# main_board.net
KiCad netlist of a schematic drawn in EAGLE
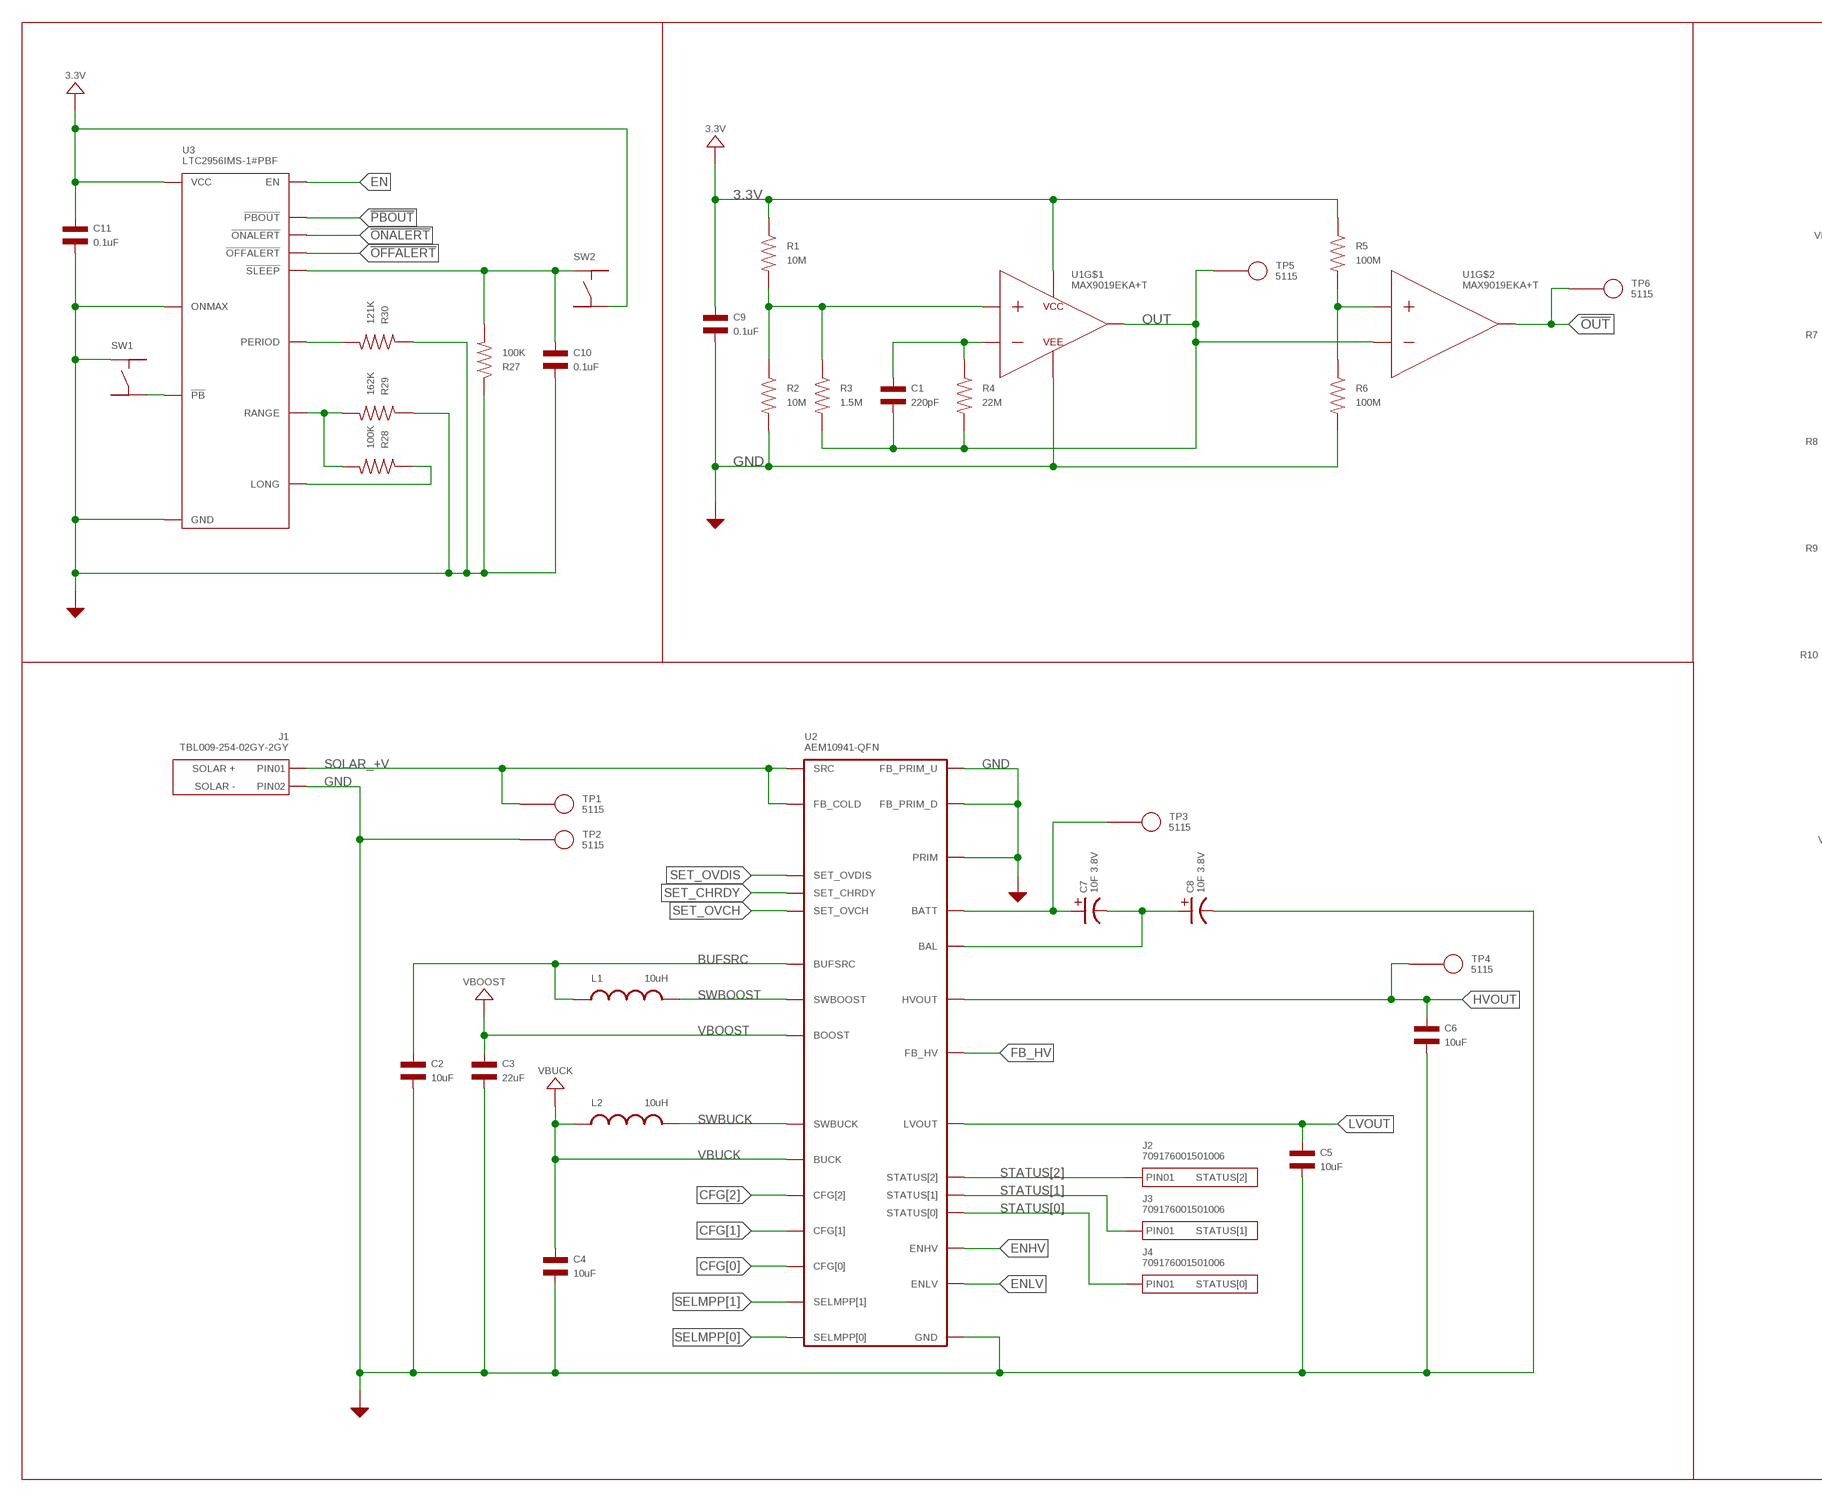
[diagram p0: schematic, sheet 1, part 1 of 2]
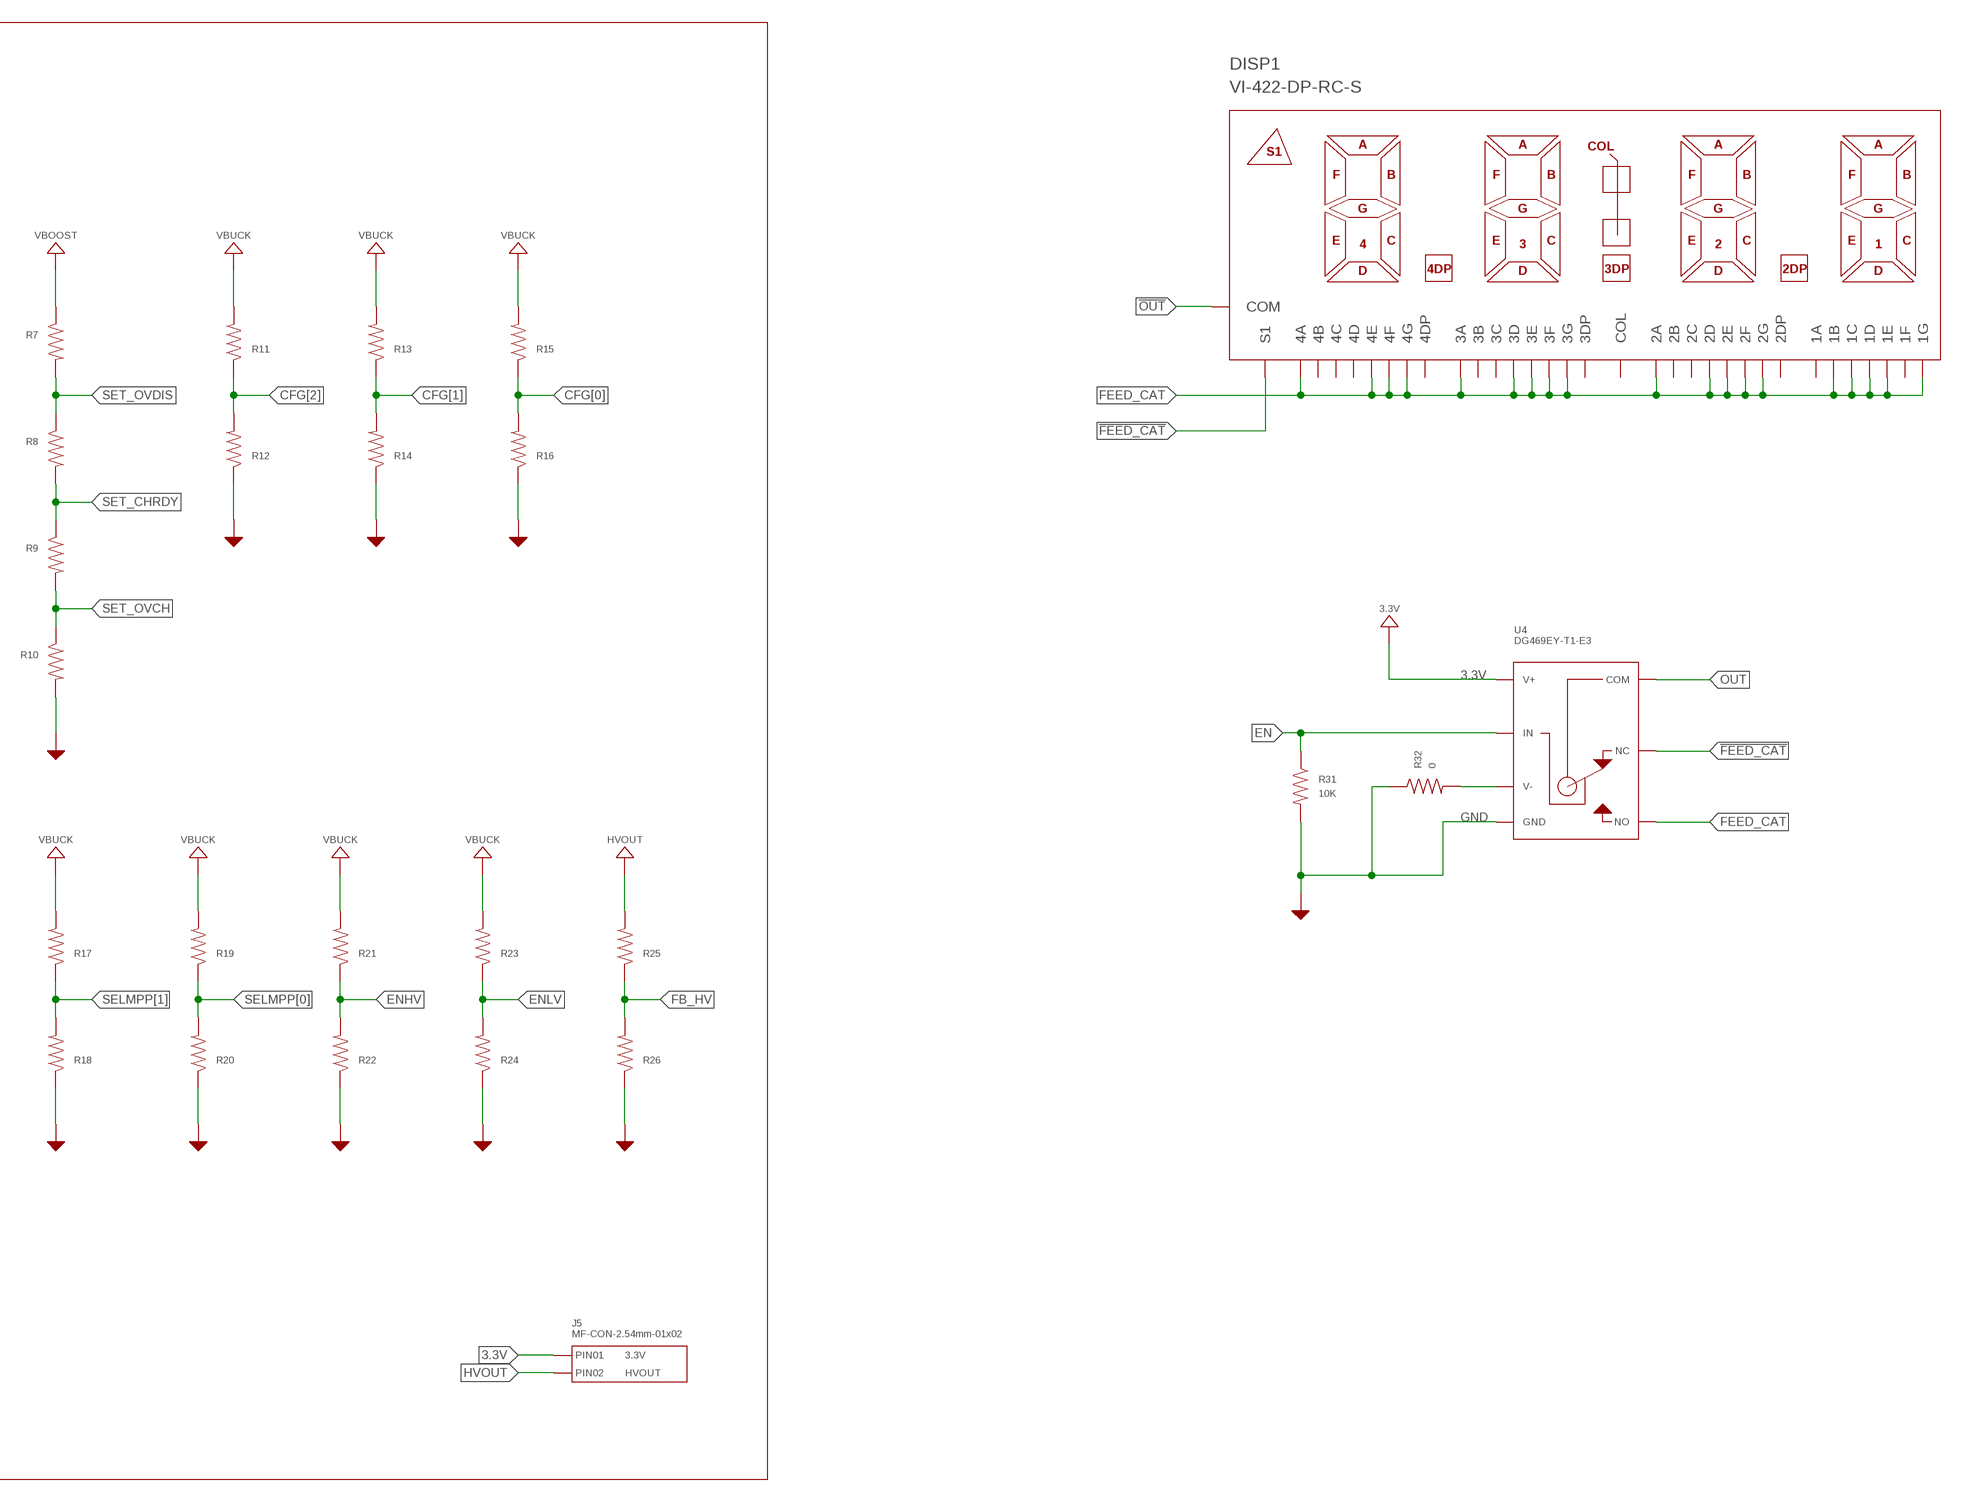
[diagram p1: schematic, sheet 1, part 2 of 2]

(export (version "E")
  (design (tool "Eeschema 10.0.6"))
  (components
    (comp (ref "C1")
      (value "220pF")
      (footprint "eagle-import:C0805")
      (libsource (lib "eagle-import") (part "CAPACITOR_NP_0805"))
    )
    (comp (ref "C2")
      (value "10uF")
      (footprint "eagle-import:C0603")
      (fields (field (name "MPN") "C1608X5R1A106M080AC"))
      (libsource (lib "eagle-import") (part "CAPACITOR_NP_0603"))
    )
    (comp (ref "C3")
      (value "22uF")
      (footprint "eagle-import:C0603")
      (fields (field (name "MPN") "GRM188R61A226ME15D"))
      (libsource (lib "eagle-import") (part "CAPACITOR_NP_0603"))
    )
    (comp (ref "C4")
      (value "10uF")
      (footprint "eagle-import:C0603")
      (fields (field (name "MPN") "C1608X5R1A106M080AC"))
      (libsource (lib "eagle-import") (part "CAPACITOR_NP_0603"))
    )
    (comp (ref "C5")
      (value "10uF")
      (footprint "eagle-import:C0603")
      (fields (field (name "MPN") "C1608X5R1A106M080AC"))
      (libsource (lib "eagle-import") (part "CAPACITOR_NP_0603"))
    )
    (comp (ref "C6")
      (value "10uF")
      (footprint "eagle-import:C0603")
      (fields (field (name "MPN") "C1608X5R1A106M080AC"))
      (libsource (lib "eagle-import") (part "CAPACITOR_NP_0603"))
    )
    (comp (ref "C7")
      (value "10F 3.8V")
      (footprint "eagle-import:12.5MM_CAP_PTH")
      (fields (field (name "MPN") "HSL0814-3R8106-R"))
      (libsource (lib "eagle-import") (part "CAPACITOR_POLARIZED_12.5MM_PTH"))
    )
    (comp (ref "C8")
      (value "10F 3.8V")
      (footprint "eagle-import:12.5MM_CAP_PTH")
      (fields (field (name "MPN") "HSL0814-3R8106-R"))
      (libsource (lib "eagle-import") (part "CAPACITOR_POLARIZED_12.5MM_PTH"))
    )
    (comp (ref "C9")
      (value "0.1uF")
      (footprint "eagle-import:C0603")
      (libsource (lib "eagle-import") (part "CAPACITOR_NP_0603"))
    )
    (comp (ref "C10")
      (value "0.1uF")
      (footprint "eagle-import:C0603")
      (libsource (lib "eagle-import") (part "CAPACITOR_NP_0603"))
    )
    (comp (ref "C11")
      (value "0.1uF")
      (footprint "eagle-import:C0603")
      (libsource (lib "eagle-import") (part "CAPACITOR_NP_0603"))
    )
    (comp (ref "DISP1")
      (value "VI-422-DP-RC-S")
      (footprint "eagle-import:VI-422-DP-RC-S")
      (libsource (lib "eagle-import") (part "VI-422-DP-RC-S"))
    )
    (comp (ref "J1")
      (value "TBL009-254-02GY-2GY")
      (footprint "eagle-import:TBL009-254-02GY-2GY")
      (fields (field (name "LABEL01") "SOLAR +") (field (name "LABEL02") "SOLAR -"))
      (libsource (lib "eagle-import") (part "CON_01X02_TBL009-254-02GY-2GY"))
    )
    (comp (ref "J2")
      (value "709176001501006")
      (footprint "eagle-import:709176001501006")
      (fields (field (name "LABEL01") "STATUS[2]"))
      (libsource (lib "eagle-import") (part "CON_01X01_709176001501006"))
    )
    (comp (ref "J3")
      (value "709176001501006")
      (footprint "eagle-import:709176001501006")
      (fields (field (name "LABEL01") "STATUS[1]"))
      (libsource (lib "eagle-import") (part "CON_01X01_709176001501006"))
    )
    (comp (ref "J4")
      (value "709176001501006")
      (footprint "eagle-import:709176001501006")
      (fields (field (name "LABEL01") "STATUS[0]"))
      (libsource (lib "eagle-import") (part "CON_01X01_709176001501006"))
    )
    (comp (ref "J5")
      (value "MF-CON-2.54mm-01x02")
      (footprint "eagle-import:PTH_2.54MM_01X02")
      (fields
        (field (name "HOUSEPART") "YES")
        (field (name "LABEL01") "3.3V")
        (field (name "LABEL02") "HVOUT")
      )
      (libsource (lib "eagle-import") (part "CON_01X02_PTH_2.54MM"))
    )
    (comp (ref "L1")
      (value "10uH")
      (footprint "eagle-import:LPS4012")
      (fields (field (name "MPN") "LPS4012-103MRC "))
      (libsource (lib "eagle-import") (part "INDUCTORLPS4012"))
    )
    (comp (ref "L2")
      (value "10uH")
      (footprint "eagle-import:0603")
      (fields (field (name "MPN") "MLZ1608M100WT"))
      (libsource (lib "eagle-import") (part "INDUCTOR_0603"))
    )
    (comp (ref "R1")
      (value "10M")
      (footprint "eagle-import:R0805")
      (libsource (lib "eagle-import") (part "RESISTOR_0805"))
    )
    (comp (ref "R2")
      (value "10M")
      (footprint "eagle-import:R0805")
      (libsource (lib "eagle-import") (part "RESISTOR_0805"))
    )
    (comp (ref "R3")
      (value "1.5M")
      (footprint "eagle-import:R0805")
      (libsource (lib "eagle-import") (part "RESISTOR_0805"))
    )
    (comp (ref "R4")
      (value "22M")
      (footprint "eagle-import:R0805")
      (libsource (lib "eagle-import") (part "RESISTOR_0805"))
    )
    (comp (ref "R5")
      (value "100M")
      (footprint "eagle-import:R0805")
      (libsource (lib "eagle-import") (part "RESISTOR_0805"))
    )
    (comp (ref "R6")
      (value "100M")
      (footprint "eagle-import:R0805")
      (libsource (lib "eagle-import") (part "RESISTOR_0805"))
    )
    (comp (ref "R7")
      (value "RESISTOR_0805")
      (footprint "eagle-import:R0805")
      (fields (field (name "POPULATE") "0"))
      (libsource (lib "eagle-import") (part "RESISTOR_0805"))
    )
    (comp (ref "R8")
      (value "RESISTOR_0805")
      (footprint "eagle-import:R0805")
      (fields (field (name "POPULATE") "0"))
      (libsource (lib "eagle-import") (part "RESISTOR_0805"))
    )
    (comp (ref "R9")
      (value "RESISTOR_0805")
      (footprint "eagle-import:R0805")
      (fields (field (name "POPULATE") "0"))
      (libsource (lib "eagle-import") (part "RESISTOR_0805"))
    )
    (comp (ref "R10")
      (value "RESISTOR_0805")
      (footprint "eagle-import:R0805")
      (fields (field (name "POPULATE") "0"))
      (libsource (lib "eagle-import") (part "RESISTOR_0805"))
    )
    (comp (ref "R11")
      (value "RESISTOR_0805")
      (footprint "eagle-import:R0805")
      (fields (field (name "POPULATE") "0"))
      (libsource (lib "eagle-import") (part "RESISTOR_0805"))
    )
    (comp (ref "R12")
      (value "RESISTOR_0805")
      (footprint "eagle-import:R0805")
      (fields (field (name "POPULATE") "0"))
      (libsource (lib "eagle-import") (part "RESISTOR_0805"))
    )
    (comp (ref "R13")
      (value "RESISTOR_0805")
      (footprint "eagle-import:R0805")
      (fields (field (name "POPULATE") "0"))
      (libsource (lib "eagle-import") (part "RESISTOR_0805"))
    )
    (comp (ref "R14")
      (value "RESISTOR_0805")
      (footprint "eagle-import:R0805")
      (fields (field (name "POPULATE") "0"))
      (libsource (lib "eagle-import") (part "RESISTOR_0805"))
    )
    (comp (ref "R15")
      (value "RESISTOR_0805")
      (footprint "eagle-import:R0805")
      (fields (field (name "POPULATE") "0"))
      (libsource (lib "eagle-import") (part "RESISTOR_0805"))
    )
    (comp (ref "R16")
      (value "RESISTOR_0805")
      (footprint "eagle-import:R0805")
      (fields (field (name "POPULATE") "0"))
      (libsource (lib "eagle-import") (part "RESISTOR_0805"))
    )
    (comp (ref "R17")
      (value "RESISTOR_0805")
      (footprint "eagle-import:R0805")
      (fields (field (name "POPULATE") "0"))
      (libsource (lib "eagle-import") (part "RESISTOR_0805"))
    )
    (comp (ref "R18")
      (value "RESISTOR_0805")
      (footprint "eagle-import:R0805")
      (fields (field (name "POPULATE") "0"))
      (libsource (lib "eagle-import") (part "RESISTOR_0805"))
    )
    (comp (ref "R19")
      (value "RESISTOR_0805")
      (footprint "eagle-import:R0805")
      (fields (field (name "POPULATE") "0"))
      (libsource (lib "eagle-import") (part "RESISTOR_0805"))
    )
    (comp (ref "R20")
      (value "RESISTOR_0805")
      (footprint "eagle-import:R0805")
      (fields (field (name "POPULATE") "0"))
      (libsource (lib "eagle-import") (part "RESISTOR_0805"))
    )
    (comp (ref "R21")
      (value "RESISTOR_0805")
      (footprint "eagle-import:R0805")
      (fields (field (name "POPULATE") "0"))
      (libsource (lib "eagle-import") (part "RESISTOR_0805"))
    )
    (comp (ref "R22")
      (value "RESISTOR_0805")
      (footprint "eagle-import:R0805")
      (fields (field (name "POPULATE") "0"))
      (libsource (lib "eagle-import") (part "RESISTOR_0805"))
    )
    (comp (ref "R23")
      (value "RESISTOR_0805")
      (footprint "eagle-import:R0805")
      (fields (field (name "POPULATE") "0"))
      (libsource (lib "eagle-import") (part "RESISTOR_0805"))
    )
    (comp (ref "R24")
      (value "RESISTOR_0805")
      (footprint "eagle-import:R0805")
      (fields (field (name "POPULATE") "0"))
      (libsource (lib "eagle-import") (part "RESISTOR_0805"))
    )
    (comp (ref "R25")
      (value "RESISTOR_0805")
      (footprint "eagle-import:R0805")
      (fields (field (name "POPULATE") "0"))
      (libsource (lib "eagle-import") (part "RESISTOR_0805"))
    )
    (comp (ref "R26")
      (value "RESISTOR_0805")
      (footprint "eagle-import:R0805")
      (fields (field (name "POPULATE") "0"))
      (libsource (lib "eagle-import") (part "RESISTOR_0805"))
    )
    (comp (ref "R27")
      (value "100K")
      (footprint "eagle-import:R0805")
      (fields (field (name "HOUSEPART") "ERA-3ARB104V") (field (name "POPULATE") "0"))
      (libsource (lib "eagle-import") (part "RESISTOR_0805"))
    )
    (comp (ref "R28")
      (value "100K")
      (footprint "eagle-import:R0805")
      (fields (field (name "MPN") "ERA-3ARB104V") (field (name "POPULATE") "0"))
      (libsource (lib "eagle-import") (part "RESISTOR_0805"))
    )
    (comp (ref "R29")
      (value "162K")
      (footprint "eagle-import:R0805")
      (fields (field (name "MPN") "ERA-3AEB1623V") (field (name "POPULATE") "0"))
      (libsource (lib "eagle-import") (part "RESISTOR_0805"))
    )
    (comp (ref "R30")
      (value "121K")
      (footprint "eagle-import:R0805")
      (fields (field (name "MPN") "ERA-3AEB1213V") (field (name "POPULATE") "0"))
      (libsource (lib "eagle-import") (part "RESISTOR_0805"))
    )
    (comp (ref "R31")
      (value "10K")
      (footprint "eagle-import:R0805")
      (fields (field (name "POPULATE") "0"))
      (libsource (lib "eagle-import") (part "RESISTOR_0805"))
    )
    (comp (ref "R32")
      (value "0")
      (footprint "eagle-import:R0805")
      (fields (field (name "POPULATE") "0"))
      (libsource (lib "eagle-import") (part "RESISTOR_0805"))
    )
    (comp (ref "SW1")
      (value "TACT_4.2MM")
      (footprint "eagle-import:TACT4.2MM")
      (fields
        (field (name "HOUSEPART") "YES")
        (field (name "MPN") "MF-SW-TACT-4.2MM")
        (field (name "MPN_1") "PTS810 SJM 250 SMTR LFS")
      )
      (libsource (lib "eagle-import") (part "TACT_4.2MM"))
    )
    (comp (ref "SW2")
      (value "TACT_4.2MM")
      (footprint "eagle-import:TACT4.2MM")
      (fields
        (field (name "HOUSEPART") "YES")
        (field (name "MPN") "MF-SW-TACT-4.2MM")
        (field (name "MPN_1") "PTS810 SJM 250 SMTR LFS")
      )
      (libsource (lib "eagle-import") (part "TACT_4.2MM"))
    )
    (comp (ref "TP1")
      (value "5115")
      (footprint "eagle-import:KEYSTONE_5115-5119")
      (fields (field (name "LABEL01") "SOLAR V+"))
      (libsource (lib "eagle-import") (part "TEST_POINT_SINGLE_KEYSTONE_5115-5119"))
    )
    (comp (ref "TP2")
      (value "5115")
      (footprint "eagle-import:KEYSTONE_5115-5119")
      (fields (field (name "LABEL01") "GND"))
      (libsource (lib "eagle-import") (part "TEST_POINT_SINGLE_KEYSTONE_5115-5119"))
    )
    (comp (ref "TP3")
      (value "5115")
      (footprint "eagle-import:KEYSTONE_5115-5119")
      (fields (field (name "LABEL01") "CAP V+"))
      (libsource (lib "eagle-import") (part "TEST_POINT_SINGLE_KEYSTONE_5115-5119"))
    )
    (comp (ref "TP4")
      (value "5115")
      (footprint "eagle-import:KEYSTONE_5115-5119")
      (fields (field (name "LABEL01") "HVOUT"))
      (libsource (lib "eagle-import") (part "TEST_POINT_SINGLE_KEYSTONE_5115-5119"))
    )
    (comp (ref "TP5")
      (value "5115")
      (footprint "eagle-import:KEYSTONE_5115-5119")
      (fields (field (name "LABEL01") "OUT"))
      (libsource (lib "eagle-import") (part "TEST_POINT_SINGLE_KEYSTONE_5115-5119"))
    )
    (comp (ref "TP6")
      (value "5115")
      (footprint "eagle-import:KEYSTONE_5115-5119")
      (fields (field (name "LABEL01") "!OUT"))
      (libsource (lib "eagle-import") (part "TEST_POINT_SINGLE_KEYSTONE_5115-5119"))
    )
    (comp (ref "U1")
      (value "MAX9019EKA+T")
      (footprint "eagle-import:MAX9019EKA+T")
      (libsource (lib "eagle-import") (part "MAX9019"))
    )
    (comp (ref "U2")
      (value "AEM10941-QFN")
      (footprint "eagle-import:AEM10941_QFN-28")
      (fields (field (name "MPN") "AEM10941"))
      (libsource (lib "eagle-import") (part "AEM10941"))
    )
    (comp (ref "U3")
      (value "LTC2956IMS-1#PBF")
      (footprint "eagle-import:LTC2956_MSOP-12")
      (fields (field (name "MPN") "LTC2956IMS-1#PBF "))
      (libsource (lib "eagle-import") (part "LTC2956IMS-1#PBF"))
    )
    (comp (ref "U4")
      (value "DG469EY-T1-E3")
      (footprint "eagle-import:DG469_SOIC-8")
      (libsource (lib "eagle-import") (part "DG469EY-T1-E3"))
    )
  )
  (nets
    (net (code "1") (name "/BUFSRC") (class "Default")
      (node (ref "C2") (pin "P$1") (pinfunction "P$1_P$1") (pintype "passive"))
      (node (ref "L1") (pin "P$2") (pinfunction "P$2_P$2") (pintype "bidirectional"))
      (node (ref "U2") (pin "P$27") (pinfunction "BUFSRC_P$27") (pintype "bidirectional"))
    )
    (net (code "2") (name "/SOLAR_+V") (class "Default")
      (node (ref "J1") (pin "1A") (pinfunction "PIN1_1A") (pintype "bidirectional"))
      (node (ref "J1") (pin "1B") (pinfunction "PIN1_1B") (pintype "bidirectional"))
      (node (ref "TP1") (pin "P$1") (pinfunction "P$1_P$1") (pintype "bidirectional"))
      (node (ref "U2") (pin "P$25") (pinfunction "SRC_P$25") (pintype "bidirectional"))
      (node (ref "U2") (pin "P$26") (pinfunction "FB_COLD_P$26") (pintype "bidirectional"))
    )
    (net (code "3") (name "/STATUS[0]") (class "Default")
      (node (ref "J4") (pin "P$1") (pinfunction "PIN1_P$1") (pintype "bidirectional"))
      (node (ref "U2") (pin "P$21") (pinfunction "STATUS[0]_P$21") (pintype "bidirectional"))
    )
    (net (code "4") (name "/STATUS[1]") (class "Default")
      (node (ref "J3") (pin "P$1") (pinfunction "PIN1_P$1") (pintype "bidirectional"))
      (node (ref "U2") (pin "P$20") (pinfunction "STATUS[1]_P$20") (pintype "bidirectional"))
    )
    (net (code "5") (name "/STATUS[2]") (class "Default")
      (node (ref "J2") (pin "P$1") (pinfunction "PIN1_P$1") (pintype "bidirectional"))
      (node (ref "U2") (pin "P$19") (pinfunction "STATUS[2]_P$19") (pintype "bidirectional"))
    )
    (net (code "6") (name "/SWBOOST") (class "Default")
      (node (ref "L1") (pin "P$1") (pinfunction "P$1_P$1") (pintype "bidirectional"))
      (node (ref "U2") (pin "P$28") (pinfunction "SWBOOST_P$28") (pintype "bidirectional"))
    )
    (net (code "7") (name "/SWBUCK") (class "Default")
      (node (ref "L2") (pin "1") (pinfunction "P$1_1") (pintype "bidirectional"))
      (node (ref "U2") (pin "P$2") (pinfunction "SWBUCK_P$2") (pintype "bidirectional"))
    )
    (net (code "8") (name "/~{FEED_CAT}") (class "Default")
      (node (ref "DISP1") (pin "P$38") (pinfunction "S1_P$38") (pintype "bidirectional"))
      (node (ref "U4") (pin "P$2") (pinfunction "NC_P$2") (pintype "bidirectional"))
    )
    (net (code "9") (name "/~{OFFALERT}") (class "Default")
      (node (ref "U3") (pin "P$10") (pinfunction "~{OFFALERT}_P$10") (pintype "bidirectional"))
    )
    (net (code "10") (name "/~{ONALERT}") (class "Default")
      (node (ref "U3") (pin "P$12") (pinfunction "~{ONALERT}_P$12") (pintype "bidirectional"))
    )
    (net (code "11") (name "/~{OUT}") (class "Default")
      (node (ref "DISP1") (pin "P$1") (pinfunction "COM_P$1") (pintype "bidirectional"))
      (node (ref "DISP1") (pin "P$40") (pinfunction "COM_P$40") (pintype "bidirectional"))
      (node (ref "TP6") (pin "P$1") (pinfunction "P$1_P$1") (pintype "bidirectional"))
      (node (ref "U1") (pin "P$7") (pinfunction "OUTPUT_2_P$7") (pintype "bidirectional"))
    )
    (net (code "12") (name "/~{PBOUT}") (class "Default")
      (node (ref "U3") (pin "P$9") (pinfunction "~{PBOUT}_P$9") (pintype "bidirectional"))
    )
    (net (code "13") (name "3.3V") (class "Default")
      (node (ref "C11") (pin "P$1") (pinfunction "P$1_P$1") (pintype "passive"))
      (node (ref "C9") (pin "P$1") (pinfunction "P$1_P$1") (pintype "passive"))
      (node (ref "J5") (pin "P$1") (pinfunction "PIN1_P$1") (pintype "bidirectional"))
      (node (ref "R1") (pin "P$1") (pinfunction "P$1_P$1") (pintype "passive"))
      (node (ref "R5") (pin "P$1") (pinfunction "P$1_P$1") (pintype "passive"))
      (node (ref "SW2") (pin "P$4") (pinfunction "P$4_P$4") (pintype "bidirectional"))
      (node (ref "U1") (pin "P$8") (pinfunction "VCC_P$8") (pintype "bidirectional"))
      (node (ref "U3") (pin "P$5") (pinfunction "VCC_P$5") (pintype "bidirectional"))
      (node (ref "U4") (pin "P$4") (pinfunction "V+_P$4") (pintype "bidirectional"))
    )
    (net (code "14") (name "CFG[0]") (class "Default")
      (node (ref "R15") (pin "P$1") (pinfunction "P$1_P$1") (pintype "passive"))
      (node (ref "R16") (pin "P$2") (pinfunction "P$2_P$2") (pintype "passive"))
      (node (ref "U2") (pin "P$6") (pinfunction "CFG[0]_P$6") (pintype "bidirectional"))
    )
    (net (code "15") (name "CFG[1]") (class "Default")
      (node (ref "R13") (pin "P$1") (pinfunction "P$1_P$1") (pintype "passive"))
      (node (ref "R14") (pin "P$2") (pinfunction "P$2_P$2") (pintype "passive"))
      (node (ref "U2") (pin "P$5") (pinfunction "CFG[1]_P$5") (pintype "bidirectional"))
    )
    (net (code "16") (name "CFG[2]") (class "Default")
      (node (ref "R11") (pin "P$1") (pinfunction "P$1_P$1") (pintype "passive"))
      (node (ref "R12") (pin "P$2") (pinfunction "P$2_P$2") (pintype "passive"))
      (node (ref "U2") (pin "P$4") (pinfunction "CFG[2]_P$4") (pintype "bidirectional"))
    )
    (net (code "17") (name "EN") (class "Default")
      (node (ref "R31") (pin "P$1") (pinfunction "P$1_P$1") (pintype "passive"))
      (node (ref "U3") (pin "P$8") (pinfunction "EN_P$8") (pintype "bidirectional"))
      (node (ref "U4") (pin "P$6") (pinfunction "IN_P$6") (pintype "bidirectional"))
    )
    (net (code "18") (name "ENHV") (class "Default")
      (node (ref "R21") (pin "P$1") (pinfunction "P$1_P$1") (pintype "passive"))
      (node (ref "R22") (pin "P$2") (pinfunction "P$2_P$2") (pintype "passive"))
      (node (ref "U2") (pin "P$12") (pinfunction "ENHV_P$12") (pintype "bidirectional"))
    )
    (net (code "19") (name "ENLV") (class "Default")
      (node (ref "R23") (pin "P$1") (pinfunction "P$1_P$1") (pintype "passive"))
      (node (ref "R24") (pin "P$2") (pinfunction "P$2_P$2") (pintype "passive"))
      (node (ref "U2") (pin "P$18") (pinfunction "ENLV_P$18") (pintype "bidirectional"))
    )
    (net (code "20") (name "FB_HV") (class "Default")
      (node (ref "R25") (pin "P$1") (pinfunction "P$1_P$1") (pintype "passive"))
      (node (ref "R26") (pin "P$2") (pinfunction "P$2_P$2") (pintype "passive"))
      (node (ref "U2") (pin "P$13") (pinfunction "FB_HV_P$13") (pintype "bidirectional"))
    )
    (net (code "21") (name "FEED_CAT") (class "Default")
      (node (ref "DISP1") (pin "P$10") (pinfunction "3D_P$10") (pintype "bidirectional"))
      (node (ref "DISP1") (pin "P$13") (pinfunction "2E_P$13") (pintype "bidirectional"))
      (node (ref "DISP1") (pin "P$14") (pinfunction "2D_P$14") (pintype "bidirectional"))
      (node (ref "DISP1") (pin "P$17") (pinfunction "1E_P$17") (pintype "bidirectional"))
      (node (ref "DISP1") (pin "P$18") (pinfunction "1D_P$18") (pintype "bidirectional"))
      (node (ref "DISP1") (pin "P$19") (pinfunction "1C_P$19") (pintype "bidirectional"))
      (node (ref "DISP1") (pin "P$20") (pinfunction "1B_P$20") (pintype "bidirectional"))
      (node (ref "DISP1") (pin "P$23") (pinfunction "1G_P$23") (pintype "bidirectional"))
      (node (ref "DISP1") (pin "P$25") (pinfunction "2A_P$25") (pintype "bidirectional"))
      (node (ref "DISP1") (pin "P$26") (pinfunction "2F_P$26") (pintype "bidirectional"))
      (node (ref "DISP1") (pin "P$27") (pinfunction "2G_P$27") (pintype "bidirectional"))
      (node (ref "DISP1") (pin "P$30") (pinfunction "3A_P$30") (pintype "bidirectional"))
      (node (ref "DISP1") (pin "P$31") (pinfunction "3F_P$31") (pintype "bidirectional"))
      (node (ref "DISP1") (pin "P$32") (pinfunction "3G_P$32") (pintype "bidirectional"))
      (node (ref "DISP1") (pin "P$35") (pinfunction "4A_P$35") (pintype "bidirectional"))
      (node (ref "DISP1") (pin "P$36") (pinfunction "4F_P$36") (pintype "bidirectional"))
      (node (ref "DISP1") (pin "P$37") (pinfunction "4G_P$37") (pintype "bidirectional"))
      (node (ref "DISP1") (pin "P$5") (pinfunction "4E_P$5") (pintype "bidirectional"))
      (node (ref "DISP1") (pin "P$9") (pinfunction "3E_P$9") (pintype "bidirectional"))
      (node (ref "U4") (pin "P$8") (pinfunction "NO_P$8") (pintype "bidirectional"))
    )
    (net (code "22") (name "GND_RAIL") (class "Default")
      (node (ref "C10") (pin "P$2") (pinfunction "P$2_P$2") (pintype "passive"))
      (node (ref "C11") (pin "P$2") (pinfunction "P$2_P$2") (pintype "passive"))
      (node (ref "C2") (pin "P$2") (pinfunction "P$2_P$2") (pintype "passive"))
      (node (ref "C3") (pin "P$2") (pinfunction "P$2_P$2") (pintype "passive"))
      (node (ref "C4") (pin "P$2") (pinfunction "P$2_P$2") (pintype "passive"))
      (node (ref "C5") (pin "P$2") (pinfunction "P$2_P$2") (pintype "passive"))
      (node (ref "C6") (pin "P$2") (pinfunction "P$2_P$2") (pintype "passive"))
      (node (ref "C8") (pin "NEG") (pinfunction "NEG_NEG") (pintype "bidirectional"))
      (node (ref "C9") (pin "P$2") (pinfunction "P$2_P$2") (pintype "passive"))
      (node (ref "J1") (pin "2A") (pinfunction "PIN2_2A") (pintype "bidirectional"))
      (node (ref "J1") (pin "2B") (pinfunction "PIN2_2B") (pintype "bidirectional"))
      (node (ref "R10") (pin "P$2") (pinfunction "P$2_P$2") (pintype "passive"))
      (node (ref "R12") (pin "P$1") (pinfunction "P$1_P$1") (pintype "passive"))
      (node (ref "R14") (pin "P$1") (pinfunction "P$1_P$1") (pintype "passive"))
      (node (ref "R16") (pin "P$1") (pinfunction "P$1_P$1") (pintype "passive"))
      (node (ref "R18") (pin "P$1") (pinfunction "P$1_P$1") (pintype "passive"))
      (node (ref "R2") (pin "P$2") (pinfunction "P$2_P$2") (pintype "passive"))
      (node (ref "R20") (pin "P$1") (pinfunction "P$1_P$1") (pintype "passive"))
      (node (ref "R22") (pin "P$1") (pinfunction "P$1_P$1") (pintype "passive"))
      (node (ref "R24") (pin "P$1") (pinfunction "P$1_P$1") (pintype "passive"))
      (node (ref "R26") (pin "P$1") (pinfunction "P$1_P$1") (pintype "passive"))
      (node (ref "R27") (pin "P$1") (pinfunction "P$1_P$1") (pintype "passive"))
      (node (ref "R29") (pin "P$1") (pinfunction "P$1_P$1") (pintype "passive"))
      (node (ref "R30") (pin "P$1") (pinfunction "P$1_P$1") (pintype "passive"))
      (node (ref "R31") (pin "P$2") (pinfunction "P$2_P$2") (pintype "passive"))
      (node (ref "R32") (pin "P$1") (pinfunction "P$1_P$1") (pintype "passive"))
      (node (ref "R6") (pin "P$2") (pinfunction "P$2_P$2") (pintype "passive"))
      (node (ref "SW1") (pin "P$1") (pinfunction "P$1_P$1") (pintype "bidirectional"))
      (node (ref "TP2") (pin "P$1") (pinfunction "P$1_P$1") (pintype "bidirectional"))
      (node (ref "U1") (pin "P$4") (pinfunction "VEE_P$4") (pintype "bidirectional"))
      (node (ref "U2") (pin "P$10") (pinfunction "FB_PRIM_U_P$10") (pintype "bidirectional"))
      (node (ref "U2") (pin "P$17") (pinfunction "PRIM_P$17") (pintype "bidirectional"))
      (node (ref "U2") (pin "P$29") (pinfunction "GND_P$29") (pintype "bidirectional"))
      (node (ref "U2") (pin "P$9") (pinfunction "FB_PRIM_D_P$9") (pintype "bidirectional"))
      (node (ref "U3") (pin "P$1") (pinfunction "ONMAX_P$1") (pintype "bidirectional"))
      (node (ref "U3") (pin "P$6") (pinfunction "GND_P$6") (pintype "bidirectional"))
      (node (ref "U4") (pin "P$3") (pinfunction "GND_P$3") (pintype "bidirectional"))
    )
    (net (code "23") (name "HVOUT") (class "Default")
      (node (ref "C6") (pin "P$1") (pinfunction "P$1_P$1") (pintype "passive"))
      (node (ref "J5") (pin "P$2") (pinfunction "PIN2_P$2") (pintype "bidirectional"))
      (node (ref "R25") (pin "P$2") (pinfunction "P$2_P$2") (pintype "passive"))
      (node (ref "TP4") (pin "P$1") (pinfunction "P$1_P$1") (pintype "bidirectional"))
      (node (ref "U2") (pin "P$14") (pinfunction "HVOUT_P$14") (pintype "bidirectional"))
    )
    (net (code "24") (name "LVOUT") (class "Default")
      (node (ref "C5") (pin "P$1") (pinfunction "P$1_P$1") (pintype "passive"))
      (node (ref "U2") (pin "P$11") (pinfunction "LVOUT_P$11") (pintype "bidirectional"))
    )
    (net (code "25") (name "Net-(U1A-INPUT_1+)") (class "Default")
      (node (ref "R1") (pin "P$2") (pinfunction "P$2_P$2") (pintype "passive"))
      (node (ref "R2") (pin "P$1") (pinfunction "P$1_P$1") (pintype "passive"))
      (node (ref "R3") (pin "P$1") (pinfunction "P$1_P$1") (pintype "passive"))
      (node (ref "U1") (pin "P$3") (pinfunction "INPUT_1+_P$3") (pintype "bidirectional"))
    )
    (net (code "26") (name "Net-(U1A-INPUT_1-)") (class "Default")
      (node (ref "C1") (pin "P$1") (pinfunction "P$1_P$1") (pintype "passive"))
      (node (ref "R4") (pin "P$1") (pinfunction "P$1_P$1") (pintype "passive"))
      (node (ref "U1") (pin "P$2") (pinfunction "INPUT_1-_P$2") (pintype "bidirectional"))
    )
    (net (code "27") (name "Net-(U1B-INPUT_2+)") (class "Default")
      (node (ref "R5") (pin "P$2") (pinfunction "P$2_P$2") (pintype "passive"))
      (node (ref "R6") (pin "P$1") (pinfunction "P$1_P$1") (pintype "passive"))
      (node (ref "U1") (pin "P$5") (pinfunction "INPUT_2+_P$5") (pintype "bidirectional"))
    )
    (net (code "28") (name "Net-(U2-BAL)") (class "Default")
      (node (ref "C7") (pin "NEG") (pinfunction "NEG_NEG") (pintype "bidirectional"))
      (node (ref "C8") (pin "POS") (pinfunction "POS_POS") (pintype "bidirectional"))
      (node (ref "U2") (pin "P$15") (pinfunction "BAL_P$15") (pintype "bidirectional"))
    )
    (net (code "29") (name "Net-(U2-BATT)") (class "Default")
      (node (ref "C7") (pin "POS") (pinfunction "POS_POS") (pintype "bidirectional"))
      (node (ref "TP3") (pin "P$1") (pinfunction "P$1_P$1") (pintype "bidirectional"))
      (node (ref "U2") (pin "P$16") (pinfunction "BATT_P$16") (pintype "bidirectional"))
    )
    (net (code "30") (name "Net-(U3-LONG)") (class "Default")
      (node (ref "R28") (pin "P$1") (pinfunction "P$1_P$1") (pintype "passive"))
      (node (ref "U3") (pin "P$2") (pinfunction "LONG_P$2") (pintype "bidirectional"))
    )
    (net (code "31") (name "Net-(U3-PERIOD)") (class "Default")
      (node (ref "R30") (pin "P$2") (pinfunction "P$2_P$2") (pintype "passive"))
      (node (ref "U3") (pin "P$4") (pinfunction "PERIOD_P$4") (pintype "bidirectional"))
    )
    (net (code "32") (name "Net-(U3-RANGE)") (class "Default")
      (node (ref "R28") (pin "P$2") (pinfunction "P$2_P$2") (pintype "passive"))
      (node (ref "R29") (pin "P$2") (pinfunction "P$2_P$2") (pintype "passive"))
      (node (ref "U3") (pin "P$3") (pinfunction "RANGE_P$3") (pintype "bidirectional"))
    )
    (net (code "33") (name "Net-(U3-~{PB})") (class "Default")
      (node (ref "SW1") (pin "P$4") (pinfunction "P$4_P$4") (pintype "bidirectional"))
      (node (ref "U3") (pin "P$7") (pinfunction "~{PB}_P$7") (pintype "bidirectional"))
    )
    (net (code "34") (name "Net-(U3-~{SLEEP})") (class "Default")
      (node (ref "C10") (pin "P$1") (pinfunction "P$1_P$1") (pintype "passive"))
      (node (ref "R27") (pin "P$2") (pinfunction "P$2_P$2") (pintype "passive"))
      (node (ref "SW2") (pin "P$1") (pinfunction "P$1_P$1") (pintype "bidirectional"))
      (node (ref "U3") (pin "P$11") (pinfunction "~{SLEEP}_P$11") (pintype "bidirectional"))
    )
    (net (code "35") (name "Net-(U4-V-)") (class "Default")
      (node (ref "R32") (pin "P$2") (pinfunction "P$2_P$2") (pintype "passive"))
      (node (ref "U4") (pin "P$7") (pinfunction "V-_P$7") (pintype "bidirectional"))
    )
    (net (code "36") (name "OUT") (class "Default")
      (node (ref "C1") (pin "P$2") (pinfunction "P$2_P$2") (pintype "passive"))
      (node (ref "R3") (pin "P$2") (pinfunction "P$2_P$2") (pintype "passive"))
      (node (ref "R4") (pin "P$2") (pinfunction "P$2_P$2") (pintype "passive"))
      (node (ref "TP5") (pin "P$1") (pinfunction "P$1_P$1") (pintype "bidirectional"))
      (node (ref "U1") (pin "P$1") (pinfunction "OUTPUT_1_P$1") (pintype "bidirectional"))
      (node (ref "U1") (pin "P$6") (pinfunction "INPUT_2-_P$6") (pintype "bidirectional"))
      (node (ref "U4") (pin "P$1") (pinfunction "COM_P$1") (pintype "bidirectional"))
    )
    (net (code "37") (name "SELMPP[0]") (class "Default")
      (node (ref "R19") (pin "P$1") (pinfunction "P$1_P$1") (pintype "passive"))
      (node (ref "R20") (pin "P$2") (pinfunction "P$2_P$2") (pintype "passive"))
      (node (ref "U2") (pin "P$8") (pinfunction "SELMPP[0]_P$8") (pintype "bidirectional"))
    )
    (net (code "38") (name "SELMPP[1]") (class "Default")
      (node (ref "R17") (pin "P$1") (pinfunction "P$1_P$1") (pintype "passive"))
      (node (ref "R18") (pin "P$2") (pinfunction "P$2_P$2") (pintype "passive"))
      (node (ref "U2") (pin "P$7") (pinfunction "SELMPP[1]_P$7") (pintype "bidirectional"))
    )
    (net (code "39") (name "SET_CHRDY") (class "Default")
      (node (ref "R8") (pin "P$2") (pinfunction "P$2_P$2") (pintype "passive"))
      (node (ref "R9") (pin "P$1") (pinfunction "P$1_P$1") (pintype "passive"))
      (node (ref "U2") (pin "P$23") (pinfunction "SET_CHRDY_P$23") (pintype "bidirectional"))
    )
    (net (code "40") (name "SET_OVCH") (class "Default")
      (node (ref "R10") (pin "P$1") (pinfunction "P$1_P$1") (pintype "passive"))
      (node (ref "R9") (pin "P$2") (pinfunction "P$2_P$2") (pintype "passive"))
      (node (ref "U2") (pin "P$22") (pinfunction "SET_OVCH_P$22") (pintype "bidirectional"))
    )
    (net (code "41") (name "SET_OVDIS") (class "Default")
      (node (ref "R7") (pin "P$2") (pinfunction "P$2_P$2") (pintype "passive"))
      (node (ref "R8") (pin "P$1") (pinfunction "P$1_P$1") (pintype "passive"))
      (node (ref "U2") (pin "P$24") (pinfunction "SET_OVDIS_P$24") (pintype "bidirectional"))
    )
    (net (code "42") (name "VBOOST") (class "Default")
      (node (ref "C3") (pin "P$1") (pinfunction "P$1_P$1") (pintype "passive"))
      (node (ref "R7") (pin "P$1") (pinfunction "P$1_P$1") (pintype "passive"))
      (node (ref "U2") (pin "P$1") (pinfunction "BOOST_P$1") (pintype "bidirectional"))
    )
    (net (code "43") (name "VBUCK") (class "Default")
      (node (ref "C4") (pin "P$1") (pinfunction "P$1_P$1") (pintype "passive"))
      (node (ref "L2") (pin "2") (pinfunction "P$2_2") (pintype "bidirectional"))
      (node (ref "R11") (pin "P$2") (pinfunction "P$2_P$2") (pintype "passive"))
      (node (ref "R13") (pin "P$2") (pinfunction "P$2_P$2") (pintype "passive"))
      (node (ref "R15") (pin "P$2") (pinfunction "P$2_P$2") (pintype "passive"))
      (node (ref "R17") (pin "P$2") (pinfunction "P$2_P$2") (pintype "passive"))
      (node (ref "R19") (pin "P$2") (pinfunction "P$2_P$2") (pintype "passive"))
      (node (ref "R21") (pin "P$2") (pinfunction "P$2_P$2") (pintype "passive"))
      (node (ref "R23") (pin "P$2") (pinfunction "P$2_P$2") (pintype "passive"))
      (node (ref "U2") (pin "P$3") (pinfunction "BUCK_P$3") (pintype "bidirectional"))
    )
    (net (code "44") (name "unconnected-(DISP1-1A-PadP$21)") (class "Default")
      (node (ref "DISP1") (pin "P$21") (pinfunction "1A_P$21") (pintype "bidirectional"))
    )
    (net (code "45") (name "unconnected-(DISP1-1F-PadP$22)") (class "Default")
      (node (ref "DISP1") (pin "P$22") (pinfunction "1F_P$22") (pintype "bidirectional"))
    )
    (net (code "46") (name "unconnected-(DISP1-2B-PadP$24)") (class "Default")
      (node (ref "DISP1") (pin "P$24") (pinfunction "2B_P$24") (pintype "bidirectional"))
    )
    (net (code "47") (name "unconnected-(DISP1-2C-PadP$15)") (class "Default")
      (node (ref "DISP1") (pin "P$15") (pinfunction "2C_P$15") (pintype "bidirectional"))
    )
    (net (code "48") (name "unconnected-(DISP1-2DP-PadP$16)") (class "Default")
      (node (ref "DISP1") (pin "P$16") (pinfunction "2DP_P$16") (pintype "bidirectional"))
    )
    (net (code "49") (name "unconnected-(DISP1-3B-PadP$29)") (class "Default")
      (node (ref "DISP1") (pin "P$29") (pinfunction "3B_P$29") (pintype "bidirectional"))
    )
    (net (code "50") (name "unconnected-(DISP1-3C-PadP$11)") (class "Default")
      (node (ref "DISP1") (pin "P$11") (pinfunction "3C_P$11") (pintype "bidirectional"))
    )
    (net (code "51") (name "unconnected-(DISP1-3DP-PadP$12)") (class "Default")
      (node (ref "DISP1") (pin "P$12") (pinfunction "3DP_P$12") (pintype "bidirectional"))
    )
    (net (code "52") (name "unconnected-(DISP1-4B-PadP$34)") (class "Default")
      (node (ref "DISP1") (pin "P$34") (pinfunction "4B_P$34") (pintype "bidirectional"))
    )
    (net (code "53") (name "unconnected-(DISP1-4C-PadP$7)") (class "Default")
      (node (ref "DISP1") (pin "P$7") (pinfunction "4C_P$7") (pintype "bidirectional"))
    )
    (net (code "54") (name "unconnected-(DISP1-4D-PadP$6)") (class "Default")
      (node (ref "DISP1") (pin "P$6") (pinfunction "4D_P$6") (pintype "bidirectional"))
    )
    (net (code "55") (name "unconnected-(DISP1-4DP-PadP$8)") (class "Default")
      (node (ref "DISP1") (pin "P$8") (pinfunction "4DP_P$8") (pintype "bidirectional"))
    )
    (net (code "56") (name "unconnected-(DISP1-COL-PadP$28)") (class "Default")
      (node (ref "DISP1") (pin "P$28") (pinfunction "COL_P$28") (pintype "bidirectional"))
    )
    (net (code "57") (name "unconnected-(SW1-PadP$2)") (class "Default")
      (node (ref "SW1") (pin "P$2") (pinfunction "P$2_P$2") (pintype "bidirectional"))
    )
    (net (code "58") (name "unconnected-(SW1-PadP$3)") (class "Default")
      (node (ref "SW1") (pin "P$3") (pinfunction "P$3_P$3") (pintype "bidirectional"))
    )
    (net (code "59") (name "unconnected-(SW2-PadP$2)") (class "Default")
      (node (ref "SW2") (pin "P$2") (pinfunction "P$2_P$2") (pintype "bidirectional"))
    )
    (net (code "60") (name "unconnected-(SW2-PadP$3)") (class "Default")
      (node (ref "SW2") (pin "P$3") (pinfunction "P$3_P$3") (pintype "bidirectional"))
    )
  )
)
